# Rate_Controller.net
KiCad netlist of a schematic drawn in EAGLE
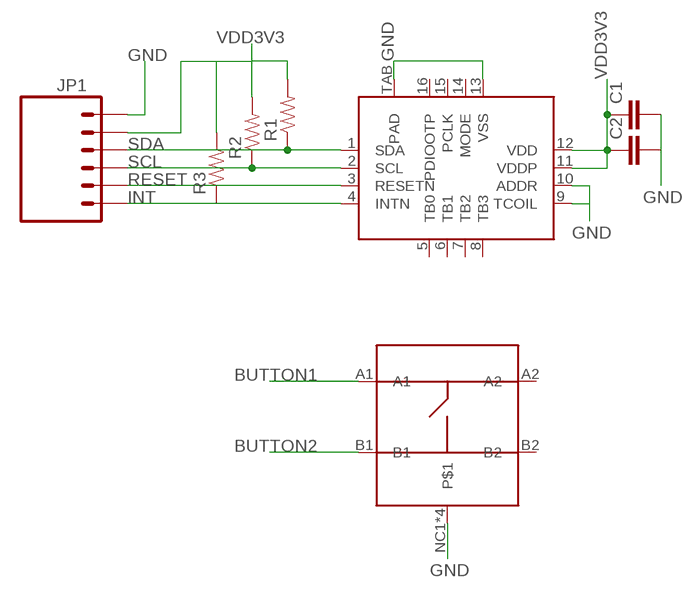
[diagram p0: schematic, sheet 1]

(export (version "E")
  (design (tool "Eeschema 10.0.6"))
  (components
    (comp (ref "C1")
      (value "CAP0805")
      (footprint "eagle-import:0805")
      (libsource (lib "eagle-import") (part "CAP0805"))
    )
    (comp (ref "C2")
      (value "CAP0805")
      (footprint "eagle-import:0805")
      (libsource (lib "eagle-import") (part "CAP0805"))
    )
    (comp (ref "JP1")
      (value "M06DUAL_ROW")
      (footprint "eagle-import:2X03")
      (libsource (lib "eagle-import") (part "M06DUAL_ROW"))
    )
    (comp (ref "R1")
      (value "RESISTOR0805-RES")
      (footprint "eagle-import:0805")
      (libsource (lib "eagle-import") (part "RESISTOR0805-RES"))
    )
    (comp (ref "R2")
      (value "RESISTOR0805-RES")
      (footprint "eagle-import:0805")
      (libsource (lib "eagle-import") (part "RESISTOR0805-RES"))
    )
    (comp (ref "R3")
      (value "RESISTOR0805-RES")
      (footprint "eagle-import:0805")
      (libsource (lib "eagle-import") (part "RESISTOR0805-RES"))
    )
    (comp (ref "U$1")
      (value "N50P105")
      (footprint "eagle-import:N50P105")
      (libsource (lib "eagle-import") (part "N50P105"))
    )
    (comp (ref "U$2")
      (value "AC5013")
      (footprint "eagle-import:QFN16")
      (libsource (lib "eagle-import") (part "AC5013"))
    )
  )
  (nets
    (net (code "1") (name "BUTTON1") (class "Default")
      (node (ref "U$1") (pin "A1") (pinfunction "A1_A1") (pintype "bidirectional"))
    )
    (net (code "2") (name "BUTTON2") (class "Default")
      (node (ref "U$1") (pin "B1") (pinfunction "B1_B1") (pintype "bidirectional"))
    )
    (net (code "3") (name "GND") (class "Default")
      (node (ref "C1") (pin "2") (pinfunction "2_2") (pintype "passive"))
      (node (ref "C2") (pin "2") (pinfunction "2_2") (pintype "passive"))
      (node (ref "JP1") (pin "1") (pinfunction "1_1") (pintype "passive"))
      (node (ref "U$1") (pin "NC1") (pinfunction "P$1_NC1") (pintype "bidirectional"))
      (node (ref "U$1") (pin "NC2") (pinfunction "P$1_NC2") (pintype "bidirectional"))
      (node (ref "U$1") (pin "NC3") (pinfunction "P$1_NC3") (pintype "bidirectional"))
      (node (ref "U$1") (pin "NC4") (pinfunction "P$1_NC4") (pintype "bidirectional"))
      (node (ref "U$2") (pin "10") (pinfunction "ADDR_10") (pintype "bidirectional"))
      (node (ref "U$2") (pin "13") (pinfunction "VSS_13") (pintype "bidirectional"))
      (node (ref "U$2") (pin "9") (pinfunction "TCOIL_9") (pintype "bidirectional"))
      (node (ref "U$2") (pin "TAB") (pinfunction "PAD_TAB") (pintype "bidirectional"))
    )
    (net (code "4") (name "INT") (class "Default")
      (node (ref "JP1") (pin "6") (pinfunction "6_6") (pintype "passive"))
      (node (ref "R3") (pin "1") (pinfunction "1_1") (pintype "passive"))
      (node (ref "U$2") (pin "4") (pinfunction "INTN_4") (pintype "bidirectional"))
    )
    (net (code "5") (name "RESET") (class "Default")
      (node (ref "JP1") (pin "5") (pinfunction "5_5") (pintype "passive"))
      (node (ref "U$2") (pin "3") (pinfunction "RESETN_3") (pintype "bidirectional"))
    )
    (net (code "6") (name "SCL") (class "Default")
      (node (ref "JP1") (pin "4") (pinfunction "4_4") (pintype "passive"))
      (node (ref "R2") (pin "1") (pinfunction "1_1") (pintype "passive"))
      (node (ref "U$2") (pin "2") (pinfunction "SCL_2") (pintype "bidirectional"))
    )
    (net (code "7") (name "SDA") (class "Default")
      (node (ref "JP1") (pin "3") (pinfunction "3_3") (pintype "passive"))
      (node (ref "R1") (pin "1") (pinfunction "1_1") (pintype "passive"))
      (node (ref "U$2") (pin "1") (pinfunction "SDA_1") (pintype "bidirectional"))
    )
    (net (code "8") (name "VDD3V3") (class "Default")
      (node (ref "C1") (pin "1") (pinfunction "1_1") (pintype "passive"))
      (node (ref "C2") (pin "1") (pinfunction "1_1") (pintype "passive"))
      (node (ref "JP1") (pin "2") (pinfunction "2_2") (pintype "passive"))
      (node (ref "R1") (pin "2") (pinfunction "2_2") (pintype "passive"))
      (node (ref "R2") (pin "2") (pinfunction "2_2") (pintype "passive"))
      (node (ref "R3") (pin "2") (pinfunction "2_2") (pintype "passive"))
      (node (ref "U$2") (pin "11") (pinfunction "VDDP_11") (pintype "bidirectional"))
      (node (ref "U$2") (pin "12") (pinfunction "VDD_12") (pintype "bidirectional"))
    )
    (net (code "9") (name "unconnected-(U$1-PadA2)") (class "Default")
      (node (ref "U$1") (pin "A2") (pinfunction "A2_A2") (pintype "bidirectional"))
    )
    (net (code "10") (name "unconnected-(U$1-PadB2)") (class "Default")
      (node (ref "U$1") (pin "B2") (pinfunction "B2_B2") (pintype "bidirectional"))
    )
    (net (code "11") (name "unconnected-(U$2-MODE-Pad14)") (class "Default")
      (node (ref "U$2") (pin "14") (pinfunction "MODE_14") (pintype "bidirectional"))
    )
    (net (code "12") (name "unconnected-(U$2-PCLK-Pad15)") (class "Default")
      (node (ref "U$2") (pin "15") (pinfunction "PCLK_15") (pintype "bidirectional"))
    )
    (net (code "13") (name "unconnected-(U$2-PDIOOTP-Pad16)") (class "Default")
      (node (ref "U$2") (pin "16") (pinfunction "PDIOOTP_16") (pintype "bidirectional"))
    )
    (net (code "14") (name "unconnected-(U$2-TB0-Pad5)") (class "Default")
      (node (ref "U$2") (pin "5") (pinfunction "TB0_5") (pintype "bidirectional"))
    )
    (net (code "15") (name "unconnected-(U$2-TB1-Pad6)") (class "Default")
      (node (ref "U$2") (pin "6") (pinfunction "TB1_6") (pintype "bidirectional"))
    )
    (net (code "16") (name "unconnected-(U$2-TB2-Pad7)") (class "Default")
      (node (ref "U$2") (pin "7") (pinfunction "TB2_7") (pintype "bidirectional"))
    )
    (net (code "17") (name "unconnected-(U$2-TB3-Pad8)") (class "Default")
      (node (ref "U$2") (pin "8") (pinfunction "TB3_8") (pintype "bidirectional"))
    )
  )
)
